# AD.net
KiCad netlist of a schematic drawn in Altium Designer
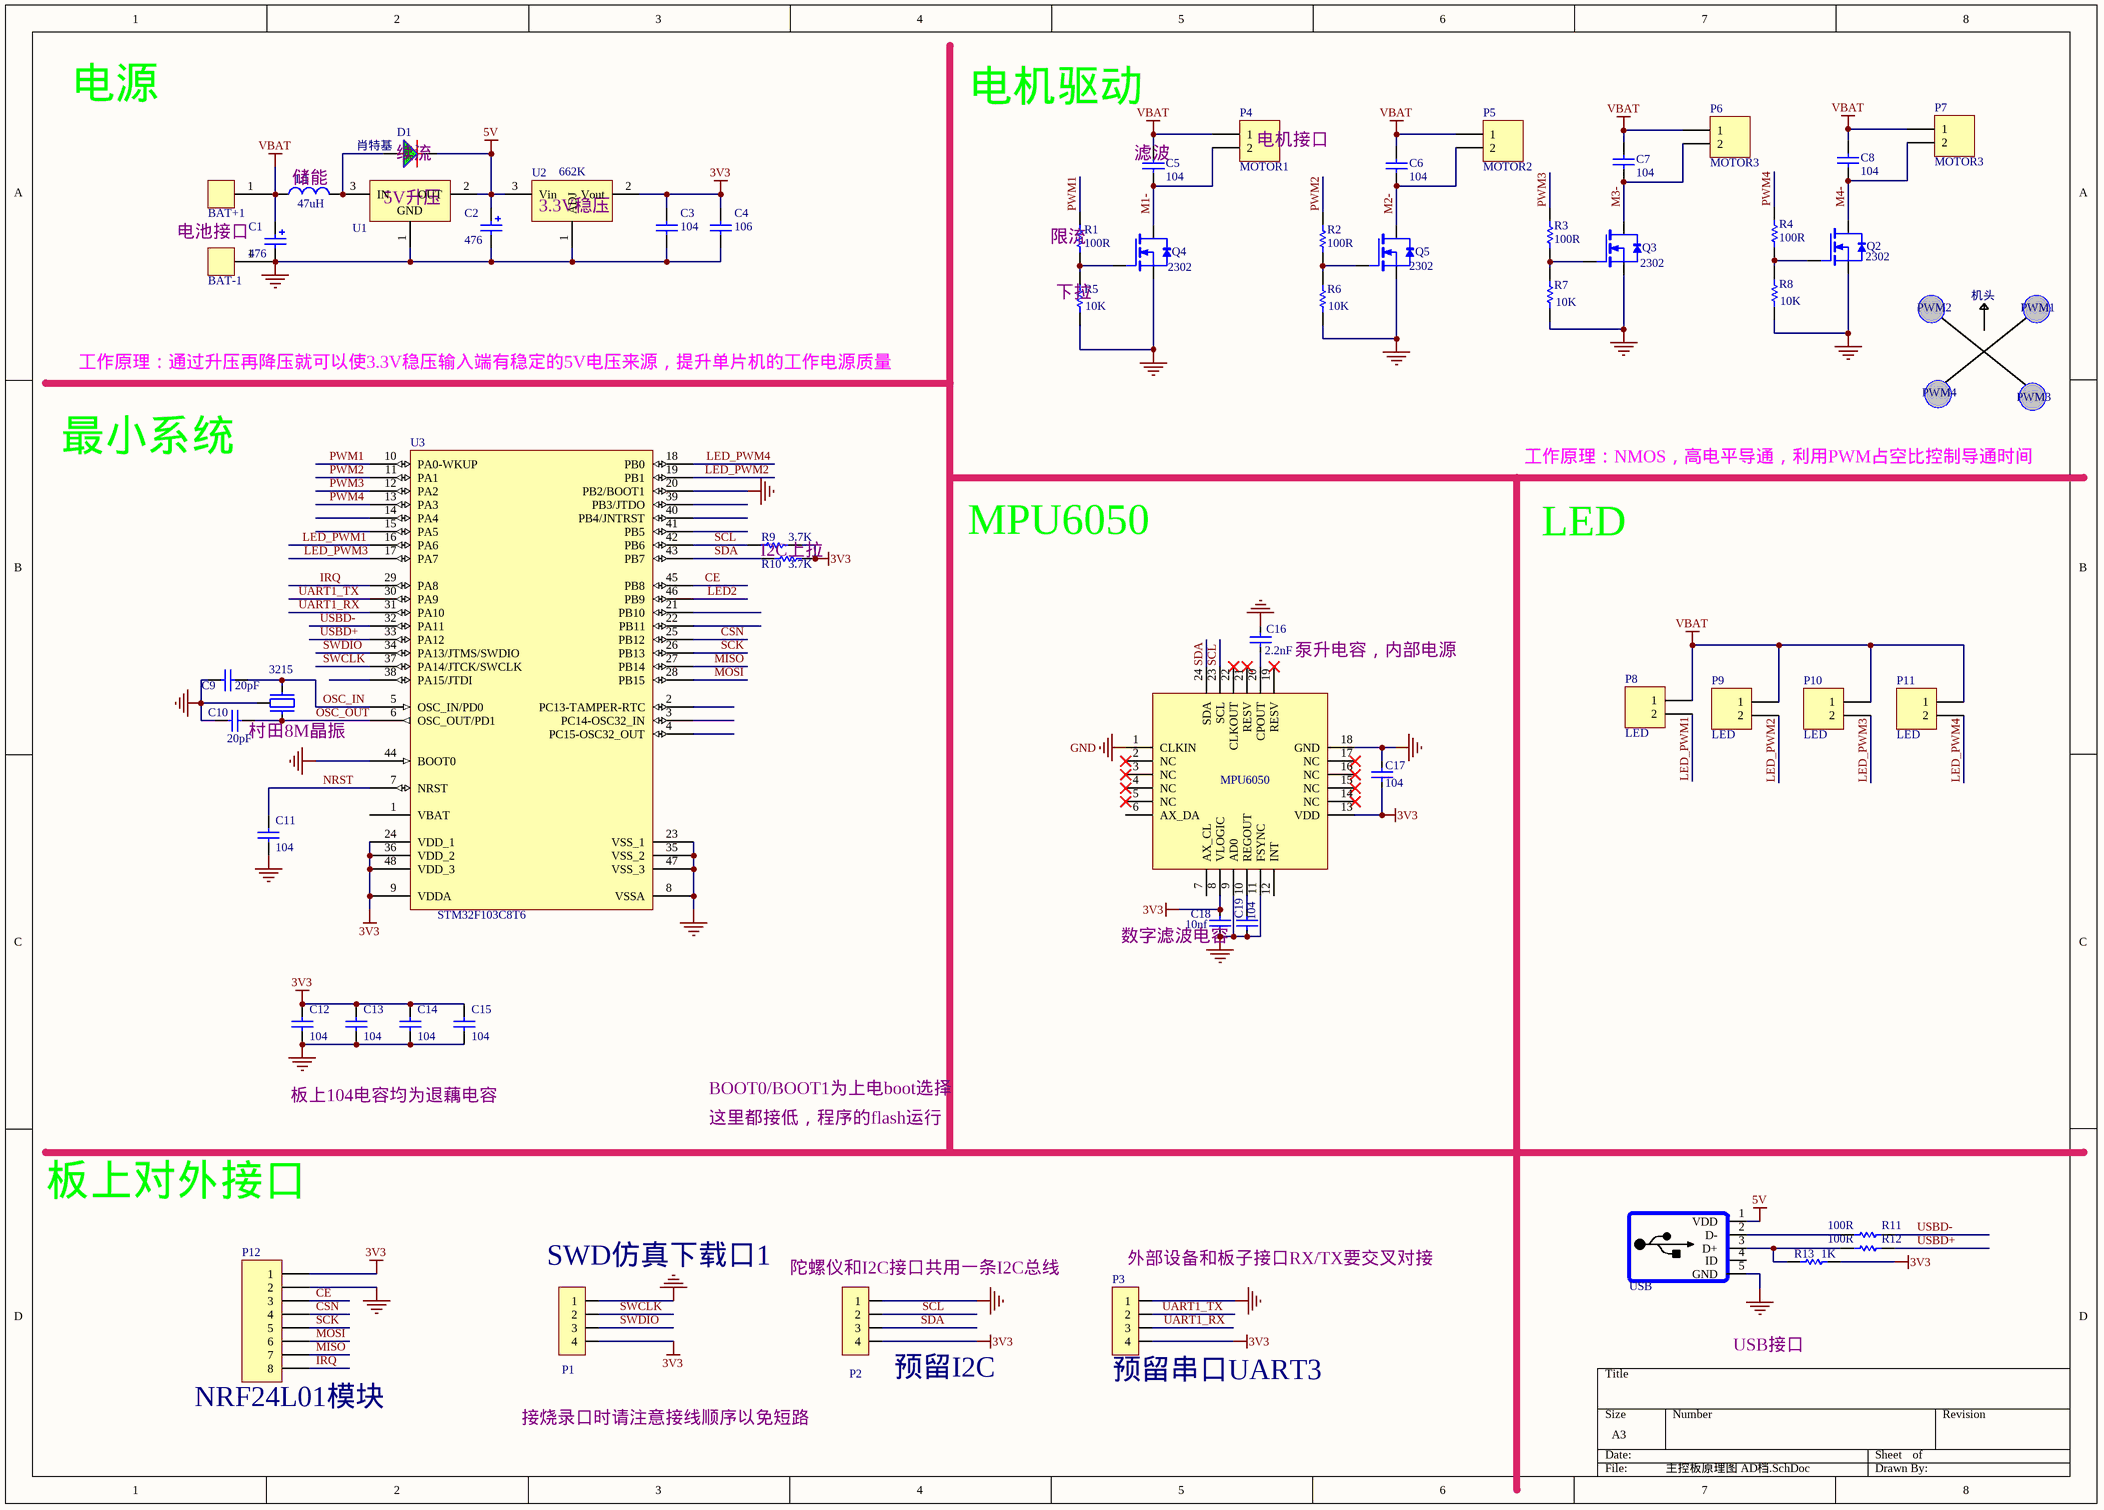
[diagram p0: 主控板原理图 AD档.SchDoc]

(export (version "E")
  (design (tool "Eeschema 10.0.6"))
  (components
    (comp (ref "*1") (value "USB") (footprint "USB") (libsource (lib "电子鼓") (part "USB")))
    (comp (ref "3215") (value "XTAL_SMT") (footprint "OSC") (libsource (lib "dx原理图库") (part "XTAL_SMT")))
    (comp (ref "BAT+1") (value "Header 1") (footprint "电池接口") (libsource (lib "quadrotor") (part "Header 1")))
    (comp (ref "BAT-1") (value "Header 1") (footprint "电池接口") (libsource (lib "quadrotor") (part "Header 1")))
    (comp (ref "C1")
      (value "476")
      (footprint "1206")
      (description "Polarized Capacitor (Radial)")
      (fields
        (field (name "VOLTAGE") "16V")
        (field (name "Comment") "Cap Tan A")
        (field (name "PUBLISHER") "Altium Limited")
      )
      (libsource (lib "ChapuIntegratedLibrary") (part "Cap Tan A"))
    )
    (comp (ref "C2")
      (value "476")
      (footprint "1206")
      (description "Polarized Capacitor (Radial)")
      (fields
        (field (name "VOLTAGE") "16V")
        (field (name "Comment") "Cap Tan A")
        (field (name "PUBLISHER") "Altium Limited")
      )
      (libsource (lib "ChapuIntegratedLibrary") (part "Cap Tan A"))
    )
    (comp (ref "C3")
      (value "104")
      (footprint "0603_C")
      (description "Polarized Capacitor (Radial)")
      (fields (field (name "Comment") "Cap Chip 1206") (field (name "PUBLISHER") "Altium Limited"))
      (libsource (lib "ChapuIntegratedLibrary") (part "Cap Chip 1206"))
    )
    (comp (ref "C4")
      (value "106")
      (footprint "0603_c")
      (description "Polarized Capacitor (Radial)")
      (fields (field (name "Comment") "Cap Chip 1206") (field (name "PUBLISHER") "Altium Limited"))
      (libsource (lib "ChapuIntegratedLibrary") (part "Cap Chip 1206"))
    )
    (comp (ref "C5")
      (value "104")
      (footprint "0603_C")
      (description "Polarized Capacitor (Radial)")
      (fields (field (name "Comment") "Cap Chip 1206") (field (name "PUBLISHER") "Altium Limited"))
      (libsource (lib "ChapuIntegratedLibrary") (part "Cap Chip 1206"))
    )
    (comp (ref "C6")
      (value "104")
      (footprint "0603_C")
      (description "Polarized Capacitor (Radial)")
      (fields (field (name "PUBLISHER") "Altium Limited"))
      (libsource (lib "ChapuIntegratedLibrary") (part "Cap Chip 1206"))
    )
    (comp (ref "C7")
      (value "104")
      (footprint "0603_C")
      (description "Polarized Capacitor (Radial)")
      (fields (field (name "Comment") "Cap Chip 1206") (field (name "PUBLISHER") "Altium Limited"))
      (libsource (lib "ChapuIntegratedLibrary") (part "Cap Chip 1206"))
    )
    (comp (ref "C8")
      (value "104")
      (footprint "0603_C")
      (description "Polarized Capacitor (Radial)")
      (fields (field (name "Comment") "Cap Chip 1206") (field (name "PUBLISHER") "Altium Limited"))
      (libsource (lib "ChapuIntegratedLibrary") (part "Cap Chip 1206"))
    )
    (comp (ref "C9") (value "20pF") (footprint "0603_C") (libsource (lib "1218迷你四轴工程_1") (part "C0603")))
    (comp (ref "C10") (value "20pF") (footprint "0603_C") (libsource (lib "1218迷你四轴工程_1") (part "C0603")))
    (comp (ref "C11") (value "104") (footprint "0603_C") (libsource (lib "1218迷你四轴工程_1") (part "C0603")))
    (comp (ref "C12") (value "104") (footprint "0603_C") (libsource (lib "1218迷你四轴工程_1") (part "C0603")))
    (comp (ref "C13") (value "104") (footprint "0603_C") (libsource (lib "1218迷你四轴工程_1") (part "C0603")))
    (comp (ref "C14") (value "104") (footprint "0603_C") (libsource (lib "1218迷你四轴工程_1") (part "C0603")))
    (comp (ref "C15") (value "104") (footprint "0603_C") (libsource (lib "1218迷你四轴工程_1") (part "C0603")))
    (comp (ref "C16")
      (value "2.2nF")
      (footprint "0603_C")
      (description "Capacitor")
      (fields (field (name "Comment") "Cap_0603"))
      (libsource (lib "SCH_Passive") (part "Cap_0603"))
    )
    (comp (ref "C17")
      (value "104")
      (footprint "0603_C")
      (description "Capacitor")
      (fields (field (name "Comment") "Cap_0603"))
      (libsource (lib "SCH_Passive") (part "Cap_0603"))
    )
    (comp (ref "C18")
      (value "10nf")
      (footprint "0603_C")
      (description "Capacitor")
      (fields (field (name "Comment") "Cap_0603"))
      (libsource (lib "SCH_Passive") (part "Cap_0603"))
    )
    (comp (ref "C19")
      (value "104")
      (footprint "0603_C")
      (description "Capacitor")
      (fields (field (name "Comment") "Cap_0603"))
      (libsource (lib "SCH_Passive") (part "Cap_0603"))
    )
    (comp (ref "D1") (value "肖特基") (footprint "0805D") (libsource (lib "*") (part "DIODE")))
    (comp (ref "L1")
      (value "47uH")
      (footprint "电感")
      (description "Inductor")
      (fields (field (name "Comment") "Inductor Chip") (field (name "PUBLISHER") "Altium Limited"))
      (libsource (lib "ChapuIntegratedLibrary") (part "Inductor Chip"))
    )
    (comp (ref "P3")
      (value "预留串口UART3")
      (footprint "1.27*4")
      (description "Header, 4-Pin, Right Angle")
      (fields (field (name "PUBLISHER") "Altium Limited"))
      (libsource (lib "linch051") (part "Header 4H"))
    )
    (comp (ref "P4")
      (value "MOTOR1")
      (footprint "2P")
      (description "Header, 2-Pin")
      (fields (field (name "PUBLISHER") "Altium Limited"))
      (libsource (lib "") (part "Header 2_1"))
    )
    (comp (ref "P5")
      (value "MOTOR2")
      (footprint "2P")
      (description "Header, 2-Pin")
      (fields (field (name "PUBLISHER") "Altium Limited"))
      (libsource (lib "") (part "Header 2_1"))
    )
    (comp (ref "P6")
      (value "MOTOR3")
      (footprint "2P")
      (description "Header, 2-Pin")
      (fields (field (name "PUBLISHER") "Altium Limited"))
      (libsource (lib "") (part "Header 2_1"))
    )
    (comp (ref "P7")
      (value "MOTOR3")
      (footprint "2P")
      (description "Header, 2-Pin")
      (fields (field (name "PUBLISHER") "Altium Limited"))
      (libsource (lib "") (part "Header 2_1"))
    )
    (comp (ref "P8")
      (value "LED")
      (footprint "2P")
      (description "Header, 2-Pin")
      (fields (field (name "PUBLISHER") "Altium Limited"))
      (libsource (lib "Miscellaneous Connectors") (part "Header 2"))
    )
    (comp (ref "P9")
      (value "LED")
      (footprint "2P")
      (description "Header, 2-Pin")
      (fields (field (name "PUBLISHER") "Altium Limited"))
      (libsource (lib "Miscellaneous Connectors") (part "Header 2"))
    )
    (comp (ref "P10")
      (value "LED")
      (footprint "2P")
      (description "Header, 2-Pin")
      (fields (field (name "PUBLISHER") "Altium Limited"))
      (libsource (lib "Miscellaneous Connectors") (part "Header 2"))
    )
    (comp (ref "P11")
      (value "LED")
      (footprint "2P")
      (description "Header, 2-Pin")
      (fields (field (name "PUBLISHER") "Altium Limited"))
      (libsource (lib "Miscellaneous Connectors") (part "Header 2"))
    )
    (comp (ref "P12")
      (value "NRF24L01模块")
      (footprint "2.4G")
      (description "Header, 8-Pin")
      (fields (field (name "PUBLISHER") "Altium Limited"))
      (libsource (lib "Miscellaneous Connectors") (part "Header 8"))
    )
    (comp (ref "Q2")
      (value "2302")
      (footprint "NMOS")
      (description "N-Channel Power MOSFET")
      (libsource (lib "1218迷你四轴工程_1") (part "N_MOS"))
    )
    (comp (ref "Q3")
      (value "2302")
      (footprint "NMOS")
      (description "N-Channel Power MOSFET")
      (libsource (lib "1218迷你四轴工程_1") (part "N_MOS"))
    )
    (comp (ref "Q4")
      (value "2302")
      (footprint "NMOS")
      (description "N-Channel MOSFET")
      (libsource (lib "1218迷你四轴工程_1") (part "N_MOS"))
    )
    (comp (ref "Q5")
      (value "2302")
      (footprint "NMOS")
      (description "N-Channel Power MOSFET")
      (libsource (lib "1218迷你四轴工程_1") (part "N_MOS"))
    )
    (comp (ref "R1")
      (value "100R")
      (footprint "0603_R")
      (description "Resistor")
      (fields (field (name "Comment") "Res1") (field (name "PUBLISHER") "Altium Limited"))
      (libsource (lib "Miscellaneous Devices") (part "Res1"))
    )
    (comp (ref "R2")
      (value "100R")
      (footprint "0603_R")
      (description "Resistor")
      (fields (field (name "Comment") "Res1") (field (name "PUBLISHER") "Altium Limited"))
      (libsource (lib "Miscellaneous Devices") (part "Res1"))
    )
    (comp (ref "R3")
      (value "100R")
      (footprint "0603_R")
      (description "Resistor")
      (fields (field (name "Comment") "Res1") (field (name "PUBLISHER") "Altium Limited"))
      (libsource (lib "Miscellaneous Devices") (part "Res1"))
    )
    (comp (ref "R4")
      (value "100R")
      (footprint "0603_R")
      (description "Resistor")
      (fields (field (name "Comment") "Res1") (field (name "PUBLISHER") "Altium Limited"))
      (libsource (lib "Miscellaneous Devices") (part "Res1"))
    )
    (comp (ref "R5")
      (value "10K")
      (footprint "0603_R")
      (description "Resistor")
      (fields (field (name "Comment") "Res1") (field (name "PUBLISHER") "Altium Limited"))
      (libsource (lib "Miscellaneous Devices") (part "Res1"))
    )
    (comp (ref "R6")
      (value "10K")
      (footprint "0603_R")
      (description "Resistor")
      (fields (field (name "Comment") "Res1") (field (name "PUBLISHER") "Altium Limited"))
      (libsource (lib "Miscellaneous Devices") (part "Res1"))
    )
    (comp (ref "R7")
      (value "10K")
      (footprint "0603_R")
      (description "Resistor")
      (fields (field (name "Comment") "Res1") (field (name "PUBLISHER") "Altium Limited"))
      (libsource (lib "Miscellaneous Devices") (part "Res1"))
    )
    (comp (ref "R8")
      (value "10K")
      (footprint "0603_R")
      (description "Resistor")
      (fields (field (name "Comment") "Res1") (field (name "PUBLISHER") "Altium Limited"))
      (libsource (lib "Miscellaneous Devices") (part "Res1"))
    )
    (comp (ref "R9")
      (value "3.7K")
      (footprint "0603_R")
      (description "Resistor")
      (fields (field (name "Comment") "Res1") (field (name "PUBLISHER") "Altium Limited"))
      (libsource (lib "Miscellaneous Devices") (part "Res1"))
    )
    (comp (ref "R10")
      (value "3.7K")
      (footprint "0603_R")
      (description "Resistor")
      (fields (field (name "Comment") "Res1") (field (name "PUBLISHER") "Altium Limited"))
      (libsource (lib "Miscellaneous Devices") (part "Res1"))
    )
    (comp (ref "R11")
      (value "100R")
      (footprint "0603_R")
      (description "Resistor")
      (fields (field (name "Comment") "Res1") (field (name "PUBLISHER") "Altium Limited"))
      (libsource (lib "Miscellaneous Devices") (part "Res1"))
    )
    (comp (ref "R12")
      (value "100R")
      (footprint "0603_R")
      (description "Resistor")
      (fields (field (name "Comment") "Res1") (field (name "PUBLISHER") "Altium Limited"))
      (libsource (lib "Miscellaneous Devices") (part "Res1"))
    )
    (comp (ref "R13")
      (value "1K")
      (footprint "0603R")
      (description "Resistor")
      (fields (field (name "Comment") "Res1") (field (name "PUBLISHER") "Altium Limited"))
      (libsource (lib "Miscellaneous Devices") (part "Res1"))
    )
    (comp (ref "SWD仿真下载口1")
      (value "P1")
      (footprint "1.27*4")
      (description "Header, 4-Pin, Right Angle")
      (fields (field (name "PUBLISHER") "Altium Limited"))
      (libsource (lib "linch051") (part "Header 4H"))
    )
    (comp (ref "U1")
      (value "7750")
      (footprint "SOT-89")
      (description "POSITIVE OUTPUT VOLTAGE")
      (libsource (lib "Q222") (part "HT7750"))
    )
    (comp (ref "U2")
      (value "662K")
      (footprint "LDO")
      (description "3-Terminal Adjustable Positive Voltage Regulator")
      (libsource (lib "稳压器件") (part "LM317"))
    )
    (comp (ref "U3")
      (value "STM32F103C8T6")
      (footprint "LQFP48")
      (libsource (lib "微型四轴") (part "STM32F103C8T6"))
    )
    (comp (ref "U4") (value "MPU6050") (footprint "QFN24") (libsource (lib "1218迷你四轴工程_1") (part "MPU6050")))
    (comp (ref "预留I2C")
      (value "P2")
      (footprint "1.27*4")
      (description "Header, 4-Pin, Right Angle")
      (fields (field (name "PUBLISHER") "Altium Limited"))
      (libsource (lib "linch051") (part "Header 4H"))
    )
  )
  (nets
    (net (code "1") (name "/CE") (class "Default")
      (node (ref "P12") (pin "3") (pinfunction "3_3") (pintype "passive"))
      (node (ref "U3") (pin "45") (pinfunction "PB8_45") (pintype "bidirectional"))
    )
    (net (code "2") (name "/CSN") (class "Default")
      (node (ref "P12") (pin "4") (pinfunction "4_4") (pintype "passive"))
      (node (ref "U3") (pin "25") (pinfunction "PB12_25") (pintype "bidirectional"))
    )
    (net (code "3") (name "/IRQ") (class "Default")
      (node (ref "P12") (pin "8") (pinfunction "8_8") (pintype "passive"))
      (node (ref "U3") (pin "29") (pinfunction "PA8_29") (pintype "bidirectional"))
    )
    (net (code "4") (name "/LED2") (class "Default")
      (node (ref "U3") (pin "46") (pinfunction "PB9_46") (pintype "bidirectional"))
    )
    (net (code "5") (name "/LED_PWM1") (class "Default")
      (node (ref "P8") (pin "2") (pinfunction "2_2") (pintype "passive"))
      (node (ref "U3") (pin "16") (pinfunction "PA6_16") (pintype "bidirectional"))
    )
    (net (code "6") (name "/LED_PWM2") (class "Default")
      (node (ref "P9") (pin "2") (pinfunction "2_2") (pintype "passive"))
      (node (ref "U3") (pin "19") (pinfunction "PB1_19") (pintype "bidirectional"))
    )
    (net (code "7") (name "/LED_PWM3") (class "Default")
      (node (ref "P10") (pin "2") (pinfunction "2_2") (pintype "passive"))
      (node (ref "U3") (pin "17") (pinfunction "PA7_17") (pintype "bidirectional"))
    )
    (net (code "8") (name "/LED_PWM4") (class "Default")
      (node (ref "P11") (pin "2") (pinfunction "2_2") (pintype "passive"))
      (node (ref "U3") (pin "18") (pinfunction "PB0_18") (pintype "bidirectional"))
    )
    (net (code "9") (name "/M1-") (class "Default")
      (node (ref "C5") (pin "1") (pinfunction "1_1") (pintype "passive"))
      (node (ref "P4") (pin "2") (pinfunction "2_2") (pintype "passive"))
      (node (ref "Q4") (pin "2") (pinfunction "D_2") (pintype "passive"))
    )
    (net (code "10") (name "/M2-") (class "Default")
      (node (ref "C6") (pin "1") (pinfunction "1_1") (pintype "passive"))
      (node (ref "P5") (pin "2") (pinfunction "2_2") (pintype "passive"))
      (node (ref "Q5") (pin "2") (pinfunction "D_2") (pintype "passive"))
    )
    (net (code "11") (name "/M3-") (class "Default")
      (node (ref "C7") (pin "1") (pinfunction "1_1") (pintype "passive"))
      (node (ref "P6") (pin "2") (pinfunction "2_2") (pintype "passive"))
      (node (ref "Q3") (pin "2") (pinfunction "D_2") (pintype "passive"))
    )
    (net (code "12") (name "/M4-") (class "Default")
      (node (ref "C8") (pin "1") (pinfunction "1_1") (pintype "passive"))
      (node (ref "P7") (pin "2") (pinfunction "2_2") (pintype "passive"))
      (node (ref "Q2") (pin "2") (pinfunction "D_2") (pintype "passive"))
    )
    (net (code "13") (name "/MISO") (class "Default")
      (node (ref "P12") (pin "7") (pinfunction "7_7") (pintype "passive"))
      (node (ref "U3") (pin "27") (pinfunction "PB14_27") (pintype "bidirectional"))
    )
    (net (code "14") (name "/MOSI") (class "Default")
      (node (ref "P12") (pin "6") (pinfunction "6_6") (pintype "passive"))
      (node (ref "U3") (pin "28") (pinfunction "PB15_28") (pintype "bidirectional"))
    )
    (net (code "15") (name "/NRST") (class "Default")
      (node (ref "C11") (pin "1") (pinfunction "1_1") (pintype "passive"))
      (node (ref "U3") (pin "7") (pinfunction "NRST_7") (pintype "bidirectional"))
    )
    (net (code "16") (name "/OSC_IN") (class "Default")
      (node (ref "3215") (pin "2") (pintype "passive"))
      (node (ref "C9") (pin "1") (pinfunction "1_1") (pintype "passive"))
      (node (ref "U3") (pin "5") (pinfunction "OSC_IN/PD0_5") (pintype "input"))
    )
    (net (code "17") (name "/OSC_OUT") (class "Default")
      (node (ref "3215") (pin "1") (pintype "passive"))
      (node (ref "C10") (pin "1") (pinfunction "1_1") (pintype "passive"))
      (node (ref "U3") (pin "6") (pinfunction "OSC_OUT/PD1_6") (pintype "output"))
    )
    (net (code "18") (name "/PWM1") (class "Default")
      (node (ref "R1") (pin "1") (pinfunction "1_1") (pintype "passive"))
      (node (ref "U3") (pin "10") (pinfunction "PA0-WKUP_10") (pintype "bidirectional"))
    )
    (net (code "19") (name "/PWM2") (class "Default")
      (node (ref "R2") (pin "1") (pinfunction "1_1") (pintype "passive"))
      (node (ref "U3") (pin "11") (pinfunction "PA1_11") (pintype "bidirectional"))
    )
    (net (code "20") (name "/PWM3") (class "Default")
      (node (ref "R3") (pin "1") (pinfunction "1_1") (pintype "passive"))
      (node (ref "U3") (pin "12") (pinfunction "PA2_12") (pintype "bidirectional"))
    )
    (net (code "21") (name "/PWM4") (class "Default")
      (node (ref "R4") (pin "1") (pinfunction "1_1") (pintype "passive"))
      (node (ref "U3") (pin "13") (pinfunction "PA3_13") (pintype "bidirectional"))
    )
    (net (code "22") (name "/SCK") (class "Default")
      (node (ref "P12") (pin "5") (pinfunction "5_5") (pintype "passive"))
      (node (ref "U3") (pin "26") (pinfunction "PB13_26") (pintype "bidirectional"))
    )
    (net (code "23") (name "/SCL") (class "Default")
      (node (ref "R9") (pin "2") (pinfunction "2_2") (pintype "passive"))
      (node (ref "U3") (pin "42") (pinfunction "PB6_42") (pintype "bidirectional"))
      (node (ref "U4") (pin "23") (pinfunction "SCL_23") (pintype "passive"))
      (node (ref "预留I2C") (pin "2") (pinfunction "2_2") (pintype "passive"))
    )
    (net (code "24") (name "/SDA") (class "Default")
      (node (ref "R10") (pin "2") (pinfunction "2_2") (pintype "passive"))
      (node (ref "U3") (pin "43") (pinfunction "PB7_43") (pintype "bidirectional"))
      (node (ref "U4") (pin "24") (pinfunction "SDA_24") (pintype "passive"))
      (node (ref "预留I2C") (pin "3") (pinfunction "3_3") (pintype "passive"))
    )
    (net (code "25") (name "/SWCLK") (class "Default")
      (node (ref "SWD仿真下载口1") (pin "2") (pinfunction "2_2") (pintype "passive"))
      (node (ref "U3") (pin "37") (pinfunction "PA14/JTCK/SWCLK_37") (pintype "bidirectional"))
    )
    (net (code "26") (name "/SWDIO") (class "Default")
      (node (ref "SWD仿真下载口1") (pin "3") (pinfunction "3_3") (pintype "passive"))
      (node (ref "U3") (pin "34") (pinfunction "PA13/JTMS/SWDIO_34") (pintype "bidirectional"))
    )
    (net (code "27") (name "/UART1_RX") (class "Default")
      (node (ref "P3") (pin "3") (pinfunction "3_3") (pintype "passive"))
      (node (ref "U3") (pin "31") (pinfunction "PA10_31") (pintype "bidirectional"))
    )
    (net (code "28") (name "/UART1_TX") (class "Default")
      (node (ref "P3") (pin "2") (pinfunction "2_2") (pintype "passive"))
      (node (ref "U3") (pin "30") (pinfunction "PA9_30") (pintype "bidirectional"))
    )
    (net (code "29") (name "/USBD+") (class "Default")
      (node (ref "R12") (pin "2") (pinfunction "2_2") (pintype "passive"))
      (node (ref "U3") (pin "33") (pinfunction "PA12_33") (pintype "bidirectional"))
    )
    (net (code "30") (name "/USBD-") (class "Default")
      (node (ref "R11") (pin "2") (pinfunction "2_2") (pintype "passive"))
      (node (ref "U3") (pin "32") (pinfunction "PA11_32") (pintype "bidirectional"))
    )
    (net (code "31") (name "3V3") (class "Default")
      (node (ref "C12") (pin "1") (pinfunction "1_1") (pintype "passive"))
      (node (ref "C13") (pin "1") (pinfunction "1_1") (pintype "passive"))
      (node (ref "C14") (pin "1") (pinfunction "1_1") (pintype "passive"))
      (node (ref "C15") (pin "1") (pinfunction "1_1") (pintype "passive"))
      (node (ref "C17") (pin "1") (pinfunction "1_1") (pintype "passive"))
      (node (ref "C18") (pin "2") (pinfunction "2_2") (pintype "passive"))
      (node (ref "C3") (pin "1") (pinfunction "1_1") (pintype "passive"))
      (node (ref "C4") (pin "1") (pinfunction "1_1") (pintype "passive"))
      (node (ref "P12") (pin "1") (pinfunction "1_1") (pintype "passive"))
      (node (ref "P3") (pin "4") (pinfunction "4_4") (pintype "passive"))
      (node (ref "R10") (pin "1") (pinfunction "1_1") (pintype "passive"))
      (node (ref "R13") (pin "1") (pinfunction "1_1") (pintype "passive"))
      (node (ref "R9") (pin "1") (pinfunction "1_1") (pintype "passive"))
      (node (ref "SWD仿真下载口1") (pin "4") (pinfunction "4_4") (pintype "passive"))
      (node (ref "U2") (pin "2") (pinfunction "Vout_2") (pintype "passive"))
      (node (ref "U3") (pin "24") (pinfunction "VDD_1_24") (pintype "power_in"))
      (node (ref "U3") (pin "36") (pinfunction "VDD_2_36") (pintype "power_in"))
      (node (ref "U3") (pin "48") (pinfunction "VDD_3_48") (pintype "power_in"))
      (node (ref "U3") (pin "9") (pinfunction "VDDA_9") (pintype "power_in"))
      (node (ref "U4") (pin "13") (pinfunction "VDD_13") (pintype "passive"))
      (node (ref "U4") (pin "8") (pinfunction "VLOGIC_8") (pintype "passive"))
      (node (ref "预留I2C") (pin "4") (pinfunction "4_4") (pintype "passive"))
    )
    (net (code "32") (name "5V") (class "Default")
      (node (ref "*1") (pin "1") (pinfunction "VDD_1") (pintype "passive"))
      (node (ref "C2") (pin "2") (pinfunction "1_2") (pintype "passive"))
      (node (ref "D1") (pin "2") (pinfunction "2_2") (pintype "passive"))
      (node (ref "U1") (pin "2") (pinfunction "OUT_2") (pintype "power_in"))
      (node (ref "U2") (pin "3") (pinfunction "Vin_3") (pintype "passive"))
    )
    (net (code "33") (name "GND") (class "Default")
      (node (ref "*1") (pin "5") (pinfunction "GND_5") (pintype "passive"))
      (node (ref "3215") (pin "0") (pinfunction "0_0") (pintype "passive"))
      (node (ref "BAT-1") (pin "1") (pintype "passive"))
      (node (ref "C1") (pin "1") (pinfunction "2_1") (pintype "passive"))
      (node (ref "C10") (pin "2") (pinfunction "2_2") (pintype "passive"))
      (node (ref "C11") (pin "2") (pinfunction "2_2") (pintype "passive"))
      (node (ref "C12") (pin "2") (pinfunction "2_2") (pintype "passive"))
      (node (ref "C13") (pin "2") (pinfunction "2_2") (pintype "passive"))
      (node (ref "C14") (pin "2") (pinfunction "2_2") (pintype "passive"))
      (node (ref "C15") (pin "2") (pinfunction "2_2") (pintype "passive"))
      (node (ref "C16") (pin "2") (pinfunction "2_2") (pintype "passive"))
      (node (ref "C17") (pin "2") (pinfunction "2_2") (pintype "passive"))
      (node (ref "C18") (pin "1") (pinfunction "1_1") (pintype "passive"))
      (node (ref "C19") (pin "1") (pinfunction "1_1") (pintype "passive"))
      (node (ref "C2") (pin "1") (pinfunction "2_1") (pintype "passive"))
      (node (ref "C3") (pin "2") (pinfunction "2_2") (pintype "passive"))
      (node (ref "C4") (pin "2") (pinfunction "2_2") (pintype "passive"))
      (node (ref "C9") (pin "2") (pinfunction "2_2") (pintype "passive"))
      (node (ref "P12") (pin "2") (pinfunction "2_2") (pintype "passive"))
      (node (ref "P3") (pin "1") (pinfunction "1_1") (pintype "passive"))
      (node (ref "Q2") (pin "3") (pinfunction "S_3") (pintype "passive"))
      (node (ref "Q3") (pin "3") (pinfunction "S_3") (pintype "passive"))
      (node (ref "Q4") (pin "3") (pinfunction "S_3") (pintype "passive"))
      (node (ref "Q5") (pin "3") (pinfunction "S_3") (pintype "passive"))
      (node (ref "R5") (pin "1") (pinfunction "1_1") (pintype "passive"))
      (node (ref "R6") (pin "1") (pinfunction "1_1") (pintype "passive"))
      (node (ref "R7") (pin "1") (pinfunction "1_1") (pintype "passive"))
      (node (ref "R8") (pin "1") (pinfunction "1_1") (pintype "passive"))
      (node (ref "SWD仿真下载口1") (pin "1") (pinfunction "1_1") (pintype "passive"))
      (node (ref "U1") (pin "1") (pinfunction "GND_1") (pintype "power_in"))
      (node (ref "U2") (pin "1") (pinfunction "ADJ_1") (pintype "passive"))
      (node (ref "U3") (pin "20") (pinfunction "PB2/BOOT1_20") (pintype "bidirectional"))
      (node (ref "U3") (pin "23") (pinfunction "VSS_1_23") (pintype "power_in"))
      (node (ref "U3") (pin "35") (pinfunction "VSS_2_35") (pintype "power_in"))
      (node (ref "U3") (pin "44") (pinfunction "BOOT0_44") (pintype "input"))
      (node (ref "U3") (pin "47") (pinfunction "VSS_3_47") (pintype "power_in"))
      (node (ref "U3") (pin "8") (pinfunction "VSSA_8") (pintype "power_in"))
      (node (ref "U4") (pin "1") (pinfunction "CLKIN_1") (pintype "passive"))
      (node (ref "U4") (pin "11") (pinfunction "FSYNC_11") (pintype "passive"))
      (node (ref "U4") (pin "18") (pinfunction "GND_18") (pintype "passive"))
      (node (ref "U4") (pin "9") (pinfunction "AD0_9") (pintype "passive"))
      (node (ref "预留I2C") (pin "1") (pinfunction "1_1") (pintype "passive"))
    )
    (net (code "34") (name "Net-(*1-D+)") (class "Default")
      (node (ref "*1") (pin "3") (pinfunction "D+_3") (pintype "passive"))
      (node (ref "R12") (pin "1") (pinfunction "1_1") (pintype "passive"))
      (node (ref "R13") (pin "2") (pinfunction "2_2") (pintype "passive"))
    )
    (net (code "35") (name "Net-(*1-D-)") (class "Default")
      (node (ref "*1") (pin "2") (pinfunction "D-_2") (pintype "passive"))
      (node (ref "R11") (pin "1") (pinfunction "1_1") (pintype "passive"))
    )
    (net (code "36") (name "Net-(Q2-G)") (class "Default")
      (node (ref "Q2") (pin "1") (pinfunction "G_1") (pintype "passive"))
      (node (ref "R4") (pin "2") (pinfunction "2_2") (pintype "passive"))
      (node (ref "R8") (pin "2") (pinfunction "2_2") (pintype "passive"))
    )
    (net (code "37") (name "Net-(Q3-G)") (class "Default")
      (node (ref "Q3") (pin "1") (pinfunction "G_1") (pintype "passive"))
      (node (ref "R3") (pin "2") (pinfunction "2_2") (pintype "passive"))
      (node (ref "R7") (pin "2") (pinfunction "2_2") (pintype "passive"))
    )
    (net (code "38") (name "Net-(Q4-G)") (class "Default")
      (node (ref "Q4") (pin "1") (pinfunction "G_1") (pintype "passive"))
      (node (ref "R1") (pin "2") (pinfunction "2_2") (pintype "passive"))
      (node (ref "R5") (pin "2") (pinfunction "2_2") (pintype "passive"))
    )
    (net (code "39") (name "Net-(Q5-G)") (class "Default")
      (node (ref "Q5") (pin "1") (pinfunction "G_1") (pintype "passive"))
      (node (ref "R2") (pin "2") (pinfunction "2_2") (pintype "passive"))
      (node (ref "R6") (pin "2") (pinfunction "2_2") (pintype "passive"))
    )
    (net (code "40") (name "Net-(U1-IN)") (class "Default")
      (node (ref "D1") (pin "1") (pinfunction "1_1") (pintype "passive"))
      (node (ref "L1") (pin "2") (pinfunction "2_2") (pintype "passive"))
      (node (ref "U1") (pin "3") (pinfunction "IN_3") (pintype "power_in"))
    )
    (net (code "41") (name "Net-(U4-CPOUT)") (class "Default")
      (node (ref "C16") (pin "1") (pinfunction "1_1") (pintype "passive"))
      (node (ref "U4") (pin "20") (pinfunction "CPOUT_20") (pintype "passive"))
    )
    (net (code "42") (name "Net-(U4-REGOUT)") (class "Default")
      (node (ref "C19") (pin "2") (pinfunction "2_2") (pintype "passive"))
      (node (ref "U4") (pin "10") (pinfunction "REGOUT_10") (pintype "passive"))
    )
    (net (code "43") (name "VBAT") (class "Default")
      (node (ref "BAT+1") (pin "1") (pintype "passive"))
      (node (ref "C1") (pin "2") (pinfunction "1_2") (pintype "passive"))
      (node (ref "C5") (pin "2") (pinfunction "2_2") (pintype "passive"))
      (node (ref "C6") (pin "2") (pinfunction "2_2") (pintype "passive"))
      (node (ref "C7") (pin "2") (pinfunction "2_2") (pintype "passive"))
      (node (ref "C8") (pin "2") (pinfunction "2_2") (pintype "passive"))
      (node (ref "L1") (pin "1") (pinfunction "1_1") (pintype "passive"))
      (node (ref "P10") (pin "1") (pinfunction "1_1") (pintype "passive"))
      (node (ref "P11") (pin "1") (pinfunction "1_1") (pintype "passive"))
      (node (ref "P4") (pin "1") (pinfunction "1_1") (pintype "passive"))
      (node (ref "P5") (pin "1") (pinfunction "1_1") (pintype "passive"))
      (node (ref "P6") (pin "1") (pinfunction "1_1") (pintype "passive"))
      (node (ref "P7") (pin "1") (pinfunction "1_1") (pintype "passive"))
      (node (ref "P8") (pin "1") (pinfunction "1_1") (pintype "passive"))
      (node (ref "P9") (pin "1") (pinfunction "1_1") (pintype "passive"))
    )
    (net (code "44") (name "unconnected-(*1-ID-Pad4)") (class "Default")
      (node (ref "*1") (pin "4") (pinfunction "ID_4") (pintype "passive"))
    )
    (net (code "45") (name "unconnected-(U3-PA4-Pad14)") (class "Default")
      (node (ref "U3") (pin "14") (pinfunction "PA4_14") (pintype "bidirectional"))
    )
    (net (code "46") (name "unconnected-(U3-PA5-Pad15)") (class "Default")
      (node (ref "U3") (pin "15") (pinfunction "PA5_15") (pintype "bidirectional"))
    )
    (net (code "47") (name "unconnected-(U3-PA15{slash}JTDI-Pad38)") (class "Default")
      (node (ref "U3") (pin "38") (pinfunction "PA15/JTDI_38") (pintype "bidirectional"))
    )
    (net (code "48") (name "unconnected-(U3-PB3{slash}JTDO-Pad39)") (class "Default")
      (node (ref "U3") (pin "39") (pinfunction "PB3/JTDO_39") (pintype "bidirectional"))
    )
    (net (code "49") (name "unconnected-(U3-PB4{slash}JNTRST-Pad40)") (class "Default")
      (node (ref "U3") (pin "40") (pinfunction "PB4/JNTRST_40") (pintype "bidirectional"))
    )
    (net (code "50") (name "unconnected-(U3-PB5-Pad41)") (class "Default")
      (node (ref "U3") (pin "41") (pinfunction "PB5_41") (pintype "bidirectional"))
    )
    (net (code "51") (name "unconnected-(U3-PB10-Pad21)") (class "Default")
      (node (ref "U3") (pin "21") (pinfunction "PB10_21") (pintype "bidirectional"))
    )
    (net (code "52") (name "unconnected-(U3-PB11-Pad22)") (class "Default")
      (node (ref "U3") (pin "22") (pinfunction "PB11_22") (pintype "bidirectional"))
    )
    (net (code "53") (name "unconnected-(U3-PC13-TAMPER-RTC-Pad2)") (class "Default")
      (node (ref "U3") (pin "2") (pinfunction "PC13-TAMPER-RTC_2") (pintype "bidirectional"))
    )
    (net (code "54") (name "unconnected-(U3-PC14-OSC32_IN-Pad3)") (class "Default")
      (node (ref "U3") (pin "3") (pinfunction "PC14-OSC32_IN_3") (pintype "bidirectional"))
    )
    (net (code "55") (name "unconnected-(U3-PC15-OSC32_OUT-Pad4)") (class "Default")
      (node (ref "U3") (pin "4") (pinfunction "PC15-OSC32_OUT_4") (pintype "bidirectional"))
    )
    (net (code "56") (name "unconnected-(U3-VBAT-Pad1)") (class "Default")
      (node (ref "U3") (pin "1") (pinfunction "VBAT_1") (pintype "power_in"))
    )
    (net (code "57") (name "unconnected-(U4-AX_CL-Pad7)") (class "Default")
      (node (ref "U4") (pin "7") (pinfunction "AX_CL_7") (pintype "passive"))
    )
    (net (code "58") (name "unconnected-(U4-AX_DA-Pad6)") (class "Default")
      (node (ref "U4") (pin "6") (pinfunction "AX_DA_6") (pintype "passive"))
    )
    (net (code "59") (name "unconnected-(U4-CLKOUT-Pad22)") (class "Default")
      (node (ref "U4") (pin "22") (pinfunction "CLKOUT_22") (pintype "passive+no_connect"))
    )
    (net (code "60") (name "unconnected-(U4-INT-Pad12)") (class "Default")
      (node (ref "U4") (pin "12") (pinfunction "INT_12") (pintype "passive"))
    )
    (net (code "61") (name "unconnected-(U4-NC-Pad2)") (class "Default")
      (node (ref "U4") (pin "2") (pinfunction "NC_2") (pintype "passive+no_connect"))
    )
    (net (code "62") (name "unconnected-(U4-NC-Pad3)") (class "Default")
      (node (ref "U4") (pin "3") (pinfunction "NC_3") (pintype "passive+no_connect"))
    )
    (net (code "63") (name "unconnected-(U4-NC-Pad4)") (class "Default")
      (node (ref "U4") (pin "4") (pinfunction "NC_4") (pintype "passive+no_connect"))
    )
    (net (code "64") (name "unconnected-(U4-NC-Pad5)") (class "Default")
      (node (ref "U4") (pin "5") (pinfunction "NC_5") (pintype "passive+no_connect"))
    )
    (net (code "65") (name "unconnected-(U4-NC-Pad14)") (class "Default")
      (node (ref "U4") (pin "14") (pinfunction "NC_14") (pintype "passive+no_connect"))
    )
    (net (code "66") (name "unconnected-(U4-NC-Pad15)") (class "Default")
      (node (ref "U4") (pin "15") (pinfunction "NC_15") (pintype "passive+no_connect"))
    )
    (net (code "67") (name "unconnected-(U4-NC-Pad16)") (class "Default")
      (node (ref "U4") (pin "16") (pinfunction "NC_16") (pintype "passive+no_connect"))
    )
    (net (code "68") (name "unconnected-(U4-NC-Pad17)") (class "Default")
      (node (ref "U4") (pin "17") (pinfunction "NC_17") (pintype "passive+no_connect"))
    )
    (net (code "69") (name "unconnected-(U4-RESV-Pad19)") (class "Default")
      (node (ref "U4") (pin "19") (pinfunction "RESV_19") (pintype "passive+no_connect"))
    )
    (net (code "70") (name "unconnected-(U4-RESV-Pad21)") (class "Default")
      (node (ref "U4") (pin "21") (pinfunction "RESV_21") (pintype "passive+no_connect"))
    )
  )
)
